# Buzzer.net
KiCad netlist of a schematic drawn in Altium Designer
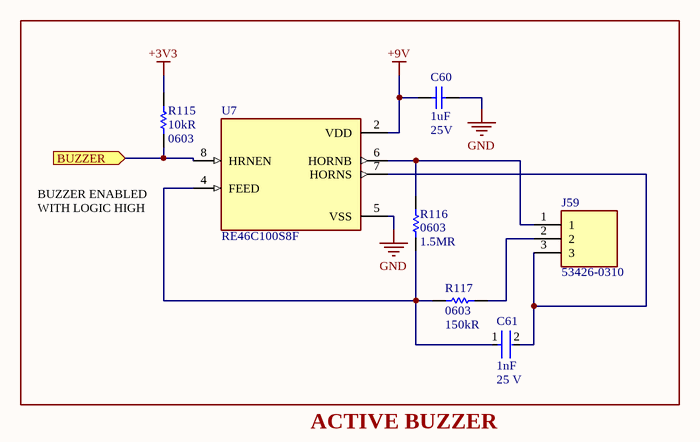
[diagram p0: Buzzer.SchDoc]

(export (version "E")
  (design (tool "Eeschema 10.0.6"))
  (components
    (comp (ref "C60")
      (value "C0603C105K3PAC7867")
      (footprint "CAPC1608X90X35LL15T15")
      (fields
        (field (name "MANUFACTURER") "Kemet")
        (field (name "MANUFACTURER PART NUMBER") "C0603C105K3PACTU")
        (field (name "CAPACITANCE") "1uF")
        (field (name "TOLERANCE") "10%")
        (field (name "VOLTAGE RATING (DC)") "25V")
      )
      (libsource (lib "Altium Content Vault") (part "CAP"))
    )
    (comp (ref "C61")
      (value "C0603C102J3GACTU")
      (footprint "FP-C0603C-CF-MFG")
      (description "CAP CER 1000PF 25V 5% NP0 0603")
      (fields
        (field (name "OCTOPART") "https://octopart.com/c0603c102j3gactu-kemet-8375722")
        (field (name "CAPACITANCE") "1nF")
        (field (name "TOLERANCE") "0.05")
        (field (name "VOLTAGE RATING") "25 V")
      )
      (libsource (lib "Altium Content Vault") (part "b4654b650e69147ec39a6b967a45e02"))
    )
    (comp (ref "J59")
      (value "53426-0310")
      (footprint "SamacSys:534260310")
      (description "Connector")
      (fields (field (name "MOUSER PART NUMBER") "538-53426-0310"))
      (libsource (lib "*") (part "53426-0310"))
    )
    (comp (ref "R115")
      (value "ERJ3EKF1002V")
      (footprint "RESC1609X55X30LL15T15")
      (description "Chip Resistor, 10 KOhm, +/- 1%, 0.1 W, -55 to 155 degC, 0603 (1608 Metric), RoHS, Tape and Reel")
      (fields
        (field (name "RESISTANCE") "10kR")
        (field (name "CASE CODE (IMPERIAL)") "0603")
        (field (name "TOLERANCE") "1%")
        (field (name "MANUFACTURER") "Panasonic")
      )
      (libsource (lib "Altium Content Vault") (part "RES-2"))
    )
    (comp (ref "R116")
      (value "ERJ-3GEYJ155V")
      (footprint "RESC1608X55X30ML15T15")
      (fields
        (field (name "MANUFACTURER") "Panasonic")
        (field (name "CASE CODE (IMPERIAL)") "0603")
        (field (name "RESISTANCE") "1.5MR")
        (field (name "TOLERANCE") "5%")
      )
      (libsource (lib "Altium Content Vault") (part "RES"))
    )
    (comp (ref "R117")
      (value "ERJ-3EKF1503V")
      (footprint "RESC1608X55X30NL15T15")
      (fields
        (field (name "MANUFACTURER") "Panasonic")
        (field (name "CASE CODE (IMPERIAL)") "0603")
        (field (name "RESISTANCE") "150kR")
        (field (name "TOLERANCE") "1%")
      )
      (libsource (lib "Altium Content Vault") (part "RES"))
    )
    (comp (ref "U7")
      (value "RE46C100S8F")
      (footprint "RE46C100S8F:SOIC127P600X175-8N")
      (fields (field (name "MF") "{'manufacturer': u'Microchip Technology'}"))
      (libsource (lib "*") (part "RE46C100S8F"))
    )
  )
  (nets
    (net (code "1") (name "+3V3") (class "Default")
      (node (ref "R115") (pin "2") (pinfunction "2_2") (pintype "passive"))
    )
    (net (code "2") (name "+9V") (class "Default")
      (node (ref "C60") (pin "2") (pinfunction "2_2") (pintype "passive"))
      (node (ref "U7") (pin "2") (pinfunction "VDD_2") (pintype "power_in"))
    )
    (net (code "3") (name "/BUZZER") (class "Default")
      (node (ref "R115") (pin "1") (pinfunction "1_1") (pintype "passive"))
      (node (ref "U7") (pin "8") (pinfunction "HRNEN_8") (pintype "input"))
    )
    (net (code "4") (name "GND") (class "Default")
      (node (ref "C60") (pin "1") (pinfunction "1_1") (pintype "passive"))
      (node (ref "U7") (pin "5") (pinfunction "VSS_5") (pintype "power_in"))
    )
    (net (code "5") (name "Net-(J59-Pad2)") (class "Default")
      (node (ref "J59") (pin "2") (pinfunction "2_2") (pintype "passive"))
      (node (ref "R117") (pin "2") (pinfunction "2_2") (pintype "passive"))
    )
    (net (code "6") (name "Net-(U7-FEED)") (class "Default")
      (node (ref "C61") (pin "1") (pinfunction "1_1") (pintype "passive"))
      (node (ref "R116") (pin "1") (pinfunction "1_1") (pintype "passive"))
      (node (ref "R117") (pin "1") (pinfunction "1_1") (pintype "passive"))
      (node (ref "U7") (pin "4") (pinfunction "FEED_4") (pintype "input"))
    )
    (net (code "7") (name "Net-(U7-HORNB)") (class "Default")
      (node (ref "J59") (pin "1") (pinfunction "1_1") (pintype "passive"))
      (node (ref "R116") (pin "2") (pinfunction "2_2") (pintype "passive"))
      (node (ref "U7") (pin "6") (pinfunction "HORNB_6") (pintype "output"))
    )
    (net (code "8") (name "Net-(U7-HORNS)") (class "Default")
      (node (ref "C61") (pin "2") (pinfunction "2_2") (pintype "passive"))
      (node (ref "J59") (pin "3") (pinfunction "3_3") (pintype "passive"))
      (node (ref "U7") (pin "7") (pinfunction "HORNS_7") (pintype "output"))
    )
  )
)
